# CPU_power.net
KiCad netlist of a schematic drawn in Altium Designer
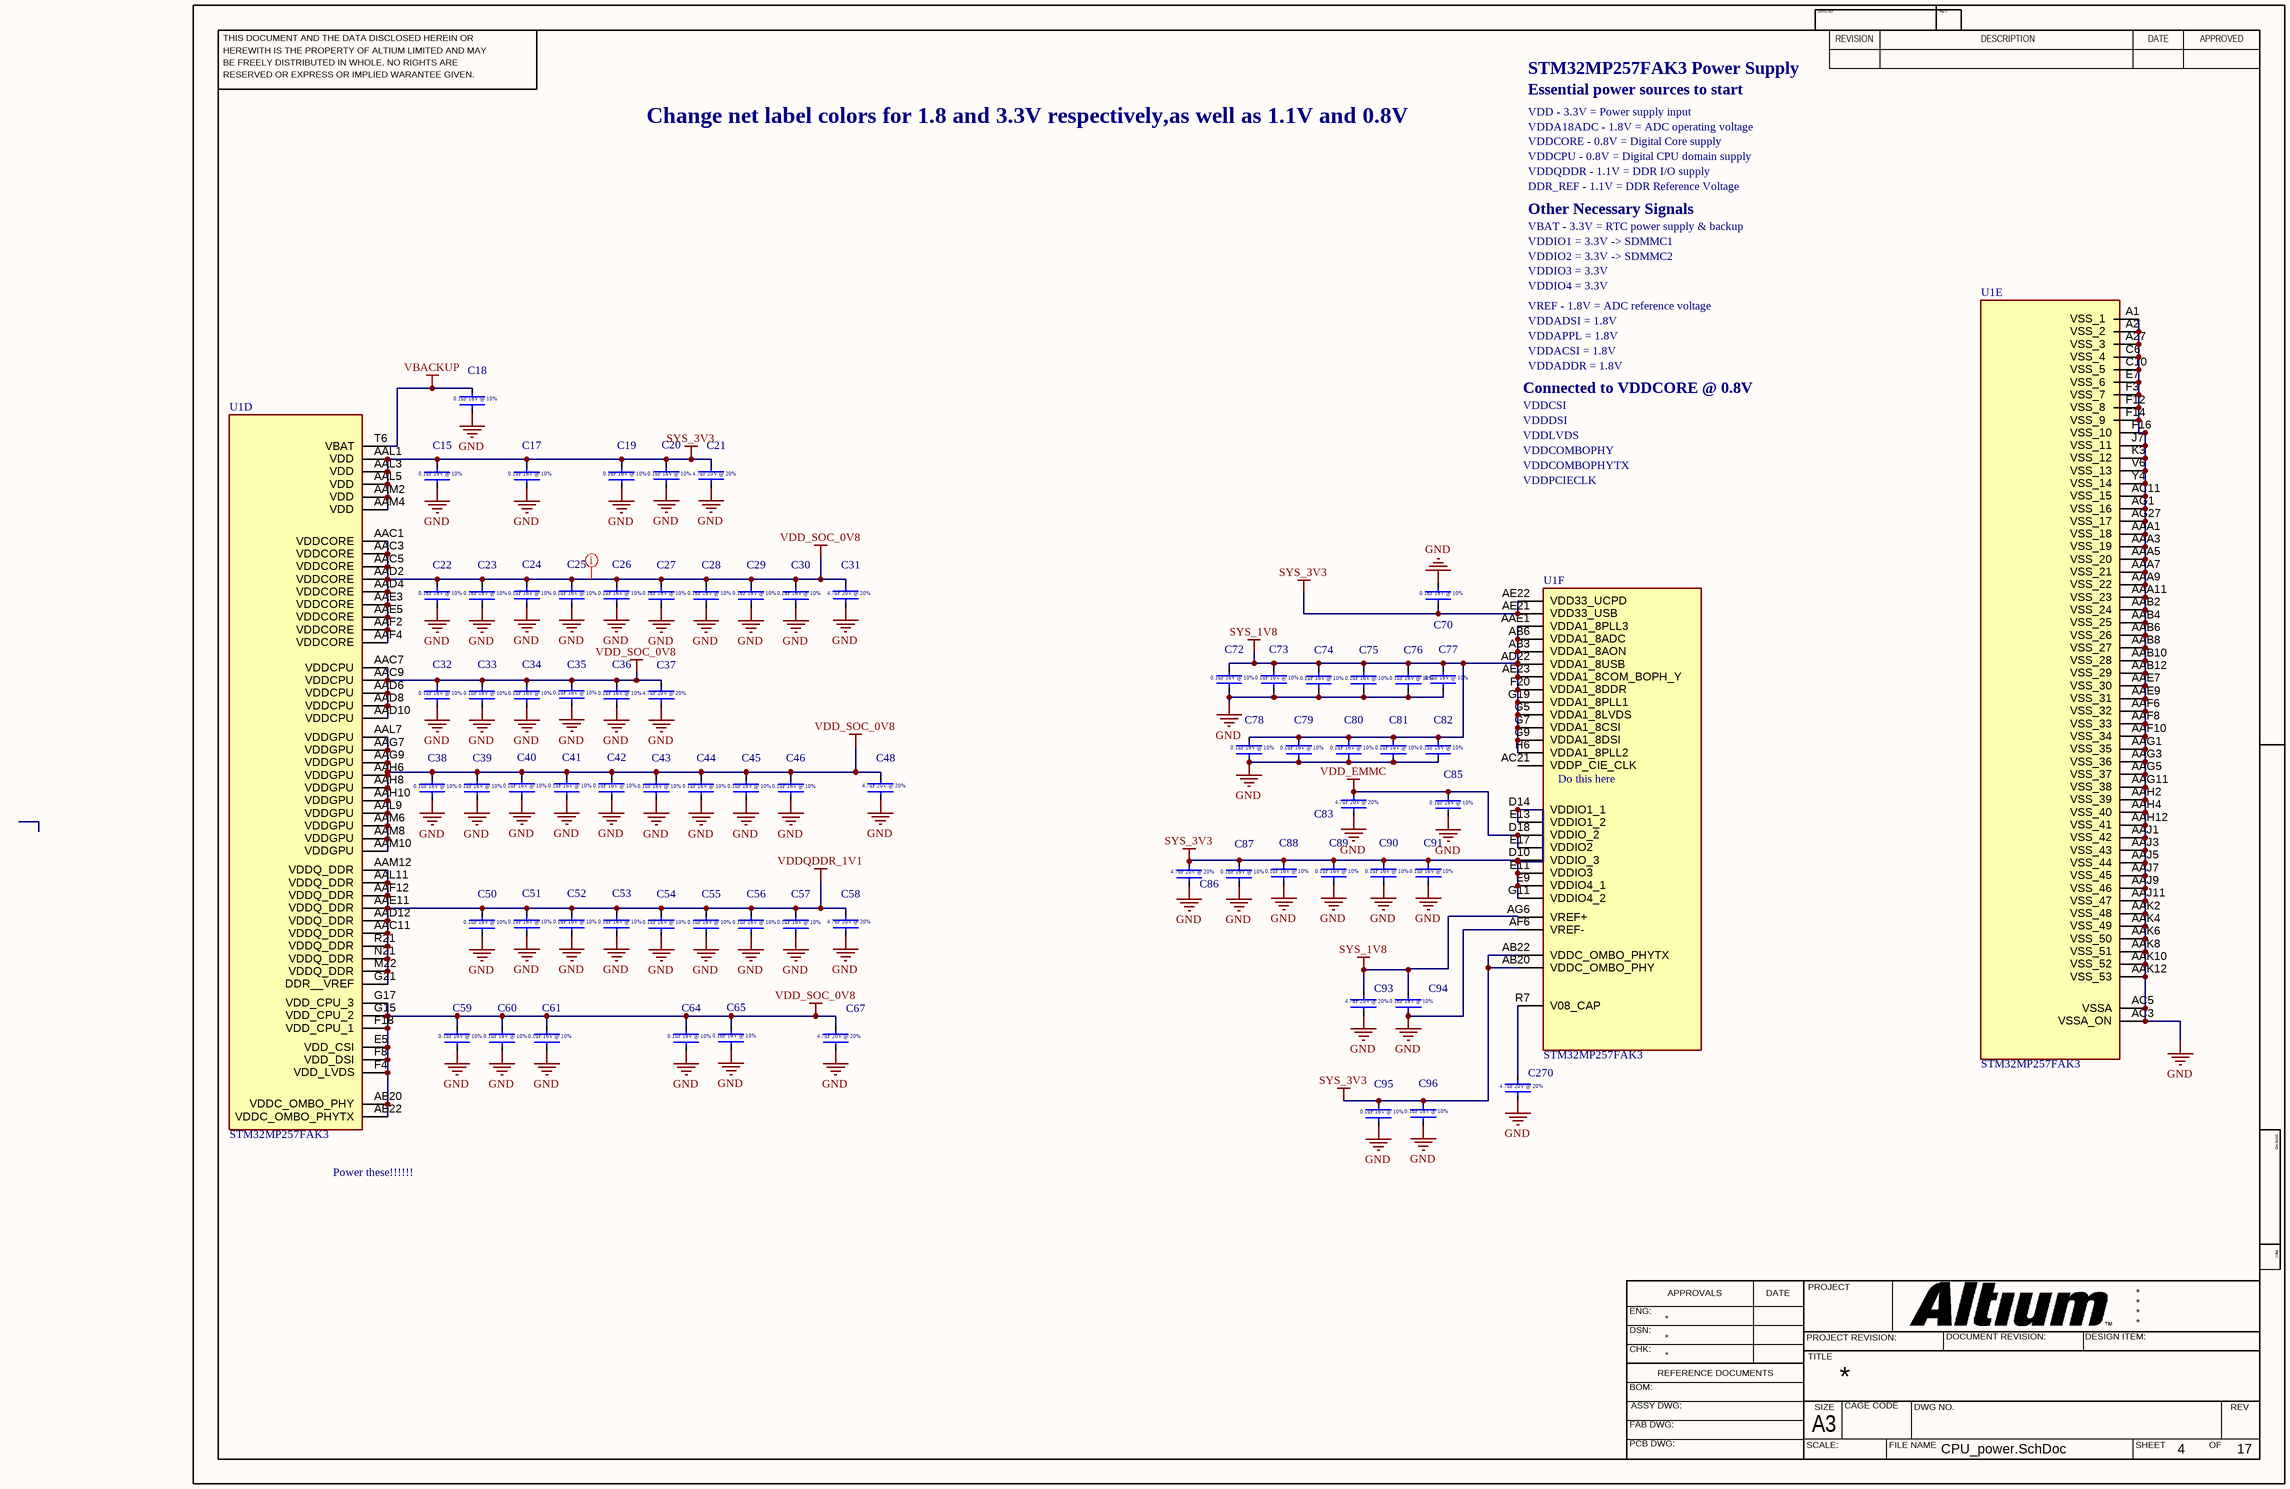
[diagram p0: CPU_power.SchDoc]

(export (version "E")
  (design (tool "Eeschema 10.0.6"))
  (components
    (comp (ref "C15")
      (value "0.1uF")
      (footprint "CAPC0603X03L")
      (libsource (lib "Gesturelink Schematic Library") (part "GRM033R61E104KE14J"))
    )
    (comp (ref "C17")
      (value "0.1uF")
      (footprint "CAPC0603X03L")
      (libsource (lib "Gesturelink Schematic Library") (part "GRM033R61E104KE14J"))
    )
    (comp (ref "C18")
      (value "0.1uF")
      (footprint "CAPC0603X03L")
      (libsource (lib "Gesturelink Schematic Library") (part "GRM033R61E104KE14J"))
    )
    (comp (ref "C19")
      (value "0.1uF")
      (footprint "CAPC0603X03L")
      (libsource (lib "Gesturelink Schematic Library") (part "GRM033R61E104KE14J"))
    )
    (comp (ref "C20")
      (value "0.1uF")
      (footprint "CAPC0603X03L")
      (libsource (lib "Gesturelink Schematic Library") (part "GRM033R61E104KE14J"))
    )
    (comp (ref "C21")
      (value "4.7uF")
      (footprint "CAPC1005X06L")
      (description "4.7 µF ±20% 16V Ceramic Capacitor X5R 0402 (1005 Metric)")
      (libsource (lib "Gesturelink Schematic Library") (part "CL05A475MO5NUNC"))
    )
    (comp (ref "C22")
      (value "0.1uF")
      (footprint "CAPC0603X03L")
      (libsource (lib "Gesturelink Schematic Library") (part "GRM033R61E104KE14J"))
    )
    (comp (ref "C23")
      (value "0.1uF")
      (footprint "CAPC0603X03L")
      (libsource (lib "Gesturelink Schematic Library") (part "GRM033R61E104KE14J"))
    )
    (comp (ref "C24")
      (value "0.1uF")
      (footprint "CAPC0603X03L")
      (libsource (lib "Gesturelink Schematic Library") (part "GRM033R61E104KE14J"))
    )
    (comp (ref "C25")
      (value "0.1uF")
      (footprint "CAPC0603X03L")
      (libsource (lib "Gesturelink Schematic Library") (part "GRM033R61E104KE14J"))
    )
    (comp (ref "C26")
      (value "0.1uF")
      (footprint "CAPC0603X03L")
      (libsource (lib "Gesturelink Schematic Library") (part "GRM033R61E104KE14J"))
    )
    (comp (ref "C27")
      (value "0.1uF")
      (footprint "CAPC0603X03L")
      (libsource (lib "Gesturelink Schematic Library") (part "GRM033R61E104KE14J"))
    )
    (comp (ref "C28")
      (value "0.1uF")
      (footprint "CAPC0603X03L")
      (libsource (lib "Gesturelink Schematic Library") (part "GRM033R61E104KE14J"))
    )
    (comp (ref "C29")
      (value "0.1uF")
      (footprint "CAPC0603X03L")
      (libsource (lib "Gesturelink Schematic Library") (part "GRM033R61E104KE14J"))
    )
    (comp (ref "C30")
      (value "0.1uF")
      (footprint "CAPC0603X03L")
      (libsource (lib "Gesturelink Schematic Library") (part "GRM033R61E104KE14J"))
    )
    (comp (ref "C31")
      (value "4.7uF")
      (footprint "CAPC1005X06L")
      (description "4.7 µF ±20% 16V Ceramic Capacitor X5R 0402 (1005 Metric)")
      (libsource (lib "Gesturelink Schematic Library") (part "CL05A475MO5NUNC"))
    )
    (comp (ref "C32")
      (value "0.1uF")
      (footprint "CAPC0603X03L")
      (libsource (lib "Gesturelink Schematic Library") (part "GRM033R61E104KE14J"))
    )
    (comp (ref "C33")
      (value "0.1uF")
      (footprint "CAPC0603X03L")
      (libsource (lib "Gesturelink Schematic Library") (part "GRM033R61E104KE14J"))
    )
    (comp (ref "C34")
      (value "0.1uF")
      (footprint "CAPC0603X03L")
      (libsource (lib "Gesturelink Schematic Library") (part "GRM033R61E104KE14J"))
    )
    (comp (ref "C35")
      (value "0.1uF")
      (footprint "CAPC0603X03L")
      (libsource (lib "Gesturelink Schematic Library") (part "GRM033R61E104KE14J"))
    )
    (comp (ref "C36")
      (value "0.1uF")
      (footprint "CAPC0603X03L")
      (libsource (lib "Gesturelink Schematic Library") (part "GRM033R61E104KE14J"))
    )
    (comp (ref "C37")
      (value "4.7uF")
      (footprint "CAPC1005X06L")
      (description "4.7 µF ±20% 16V Ceramic Capacitor X5R 0402 (1005 Metric)")
      (libsource (lib "Gesturelink Schematic Library") (part "CL05A475MO5NUNC"))
    )
    (comp (ref "C38")
      (value "0.1uF")
      (footprint "CAPC0603X03L")
      (libsource (lib "Gesturelink Schematic Library") (part "GRM033R61E104KE14J"))
    )
    (comp (ref "C39")
      (value "0.1uF")
      (footprint "CAPC0603X03L")
      (libsource (lib "Gesturelink Schematic Library") (part "GRM033R61E104KE14J"))
    )
    (comp (ref "C40")
      (value "0.1uF")
      (footprint "CAPC0603X03L")
      (libsource (lib "Gesturelink Schematic Library") (part "GRM033R61E104KE14J"))
    )
    (comp (ref "C41")
      (value "0.1uF")
      (footprint "CAPC0603X03L")
      (libsource (lib "Gesturelink Schematic Library") (part "GRM033R61E104KE14J"))
    )
    (comp (ref "C42")
      (value "0.1uF")
      (footprint "CAPC0603X03L")
      (libsource (lib "Gesturelink Schematic Library") (part "GRM033R61E104KE14J"))
    )
    (comp (ref "C43")
      (value "0.1uF")
      (footprint "CAPC0603X03L")
      (libsource (lib "Gesturelink Schematic Library") (part "GRM033R61E104KE14J"))
    )
    (comp (ref "C44")
      (value "0.1uF")
      (footprint "CAPC0603X03L")
      (libsource (lib "Gesturelink Schematic Library") (part "GRM033R61E104KE14J"))
    )
    (comp (ref "C45")
      (value "0.1uF")
      (footprint "CAPC0603X03L")
      (libsource (lib "Gesturelink Schematic Library") (part "GRM033R61E104KE14J"))
    )
    (comp (ref "C46")
      (value "0.1uF")
      (footprint "CAPC0603X03L")
      (libsource (lib "Gesturelink Schematic Library") (part "GRM033R61E104KE14J"))
    )
    (comp (ref "C48")
      (value "4.7uF")
      (footprint "CAPC1005X06L")
      (description "4.7 µF ±20% 16V Ceramic Capacitor X5R 0402 (1005 Metric)")
      (libsource (lib "Gesturelink Schematic Library") (part "CL05A475MO5NUNC"))
    )
    (comp (ref "C50")
      (value "0.1uF")
      (footprint "CAPC0603X03L")
      (libsource (lib "Gesturelink Schematic Library") (part "GRM033R61E104KE14J"))
    )
    (comp (ref "C51")
      (value "0.1uF")
      (footprint "CAPC0603X03L")
      (libsource (lib "Gesturelink Schematic Library") (part "GRM033R61E104KE14J"))
    )
    (comp (ref "C52")
      (value "0.1uF")
      (footprint "CAPC0603X03L")
      (libsource (lib "Gesturelink Schematic Library") (part "GRM033R61E104KE14J"))
    )
    (comp (ref "C53")
      (value "0.1uF")
      (footprint "CAPC0603X03L")
      (libsource (lib "Gesturelink Schematic Library") (part "GRM033R61E104KE14J"))
    )
    (comp (ref "C54")
      (value "0.1uF")
      (footprint "CAPC0603X03L")
      (libsource (lib "Gesturelink Schematic Library") (part "GRM033R61E104KE14J"))
    )
    (comp (ref "C55")
      (value "0.1uF")
      (footprint "CAPC0603X03L")
      (libsource (lib "Gesturelink Schematic Library") (part "GRM033R61E104KE14J"))
    )
    (comp (ref "C56")
      (value "0.1uF")
      (footprint "CAPC0603X03L")
      (libsource (lib "Gesturelink Schematic Library") (part "GRM033R61E104KE14J"))
    )
    (comp (ref "C57")
      (value "0.1uF")
      (footprint "CAPC0603X03L")
      (libsource (lib "Gesturelink Schematic Library") (part "GRM033R61E104KE14J"))
    )
    (comp (ref "C58")
      (value "4.7uF")
      (footprint "CAPC1005X06L")
      (description "4.7 µF ±20% 16V Ceramic Capacitor X5R 0402 (1005 Metric)")
      (libsource (lib "Gesturelink Schematic Library") (part "CL05A475MO5NUNC"))
    )
    (comp (ref "C59")
      (value "0.1uF")
      (footprint "CAPC0603X03L")
      (libsource (lib "Gesturelink Schematic Library") (part "GRM033R61E104KE14J"))
    )
    (comp (ref "C60")
      (value "0.1uF")
      (footprint "CAPC0603X03L")
      (libsource (lib "Gesturelink Schematic Library") (part "GRM033R61E104KE14J"))
    )
    (comp (ref "C61")
      (value "0.1uF")
      (footprint "CAPC0603X03L")
      (libsource (lib "Gesturelink Schematic Library") (part "GRM033R61E104KE14J"))
    )
    (comp (ref "C64")
      (value "0.1uF")
      (footprint "CAPC0603X03L")
      (libsource (lib "Gesturelink Schematic Library") (part "GRM033R61E104KE14J"))
    )
    (comp (ref "C65")
      (value "0.1uF")
      (footprint "CAPC0603X03L")
      (libsource (lib "Gesturelink Schematic Library") (part "GRM033R61E104KE14J"))
    )
    (comp (ref "C67")
      (value "4.7uF")
      (footprint "CAPC1005X06L")
      (description "4.7 µF ±20% 16V Ceramic Capacitor X5R 0402 (1005 Metric)")
      (libsource (lib "Gesturelink Schematic Library") (part "CL05A475MO5NUNC"))
    )
    (comp (ref "C70")
      (value "0.1uF")
      (footprint "CAPC0603X03L")
      (libsource (lib "Gesturelink Schematic Library") (part "GRM033R61E104KE14J"))
    )
    (comp (ref "C72")
      (value "0.1uF")
      (footprint "CAPC0603X03L")
      (libsource (lib "Gesturelink Schematic Library") (part "GRM033R61E104KE14J"))
    )
    (comp (ref "C73")
      (value "0.1uF")
      (footprint "CAPC0603X03L")
      (libsource (lib "Gesturelink Schematic Library") (part "GRM033R61E104KE14J"))
    )
    (comp (ref "C74")
      (value "0.1uF")
      (footprint "CAPC0603X03L")
      (libsource (lib "Gesturelink Schematic Library") (part "GRM033R61E104KE14J"))
    )
    (comp (ref "C75")
      (value "0.1uF")
      (footprint "CAPC0603X03L")
      (libsource (lib "Gesturelink Schematic Library") (part "GRM033R61E104KE14J"))
    )
    (comp (ref "C76")
      (value "0.1uF")
      (footprint "CAPC0603X03L")
      (libsource (lib "Gesturelink Schematic Library") (part "GRM033R61E104KE14J"))
    )
    (comp (ref "C77")
      (value "0.1uF")
      (footprint "CAPC0603X03L")
      (libsource (lib "Gesturelink Schematic Library") (part "GRM033R61E104KE14J"))
    )
    (comp (ref "C78")
      (value "0.1uF")
      (footprint "CAPC0603X03L")
      (libsource (lib "Gesturelink Schematic Library") (part "GRM033R61E104KE14J"))
    )
    (comp (ref "C79")
      (value "0.1uF")
      (footprint "CAPC0603X03L")
      (libsource (lib "Gesturelink Schematic Library") (part "GRM033R61E104KE14J"))
    )
    (comp (ref "C80")
      (value "0.1uF")
      (footprint "CAPC0603X03L")
      (libsource (lib "Gesturelink Schematic Library") (part "GRM033R61E104KE14J"))
    )
    (comp (ref "C81")
      (value "0.1uF")
      (footprint "CAPC0603X03L")
      (libsource (lib "Gesturelink Schematic Library") (part "GRM033R61E104KE14J"))
    )
    (comp (ref "C82")
      (value "0.1uF")
      (footprint "CAPC0603X03L")
      (libsource (lib "Gesturelink Schematic Library") (part "GRM033R61E104KE14J"))
    )
    (comp (ref "C83")
      (value "4.7uF")
      (footprint "CAPC1005X06L")
      (description "4.7 µF ±20% 16V Ceramic Capacitor X5R 0402 (1005 Metric)")
      (libsource (lib "Gesturelink Schematic Library") (part "CL05A475MO5NUNC"))
    )
    (comp (ref "C85")
      (value "0.1uF")
      (footprint "CAPC0603X03L")
      (libsource (lib "Gesturelink Schematic Library") (part "GRM033R61E104KE14J"))
    )
    (comp (ref "C86")
      (value "4.7uF")
      (footprint "CAPC1005X06L")
      (description "4.7 µF ±20% 16V Ceramic Capacitor X5R 0402 (1005 Metric)")
      (libsource (lib "Gesturelink Schematic Library") (part "CL05A475MO5NUNC"))
    )
    (comp (ref "C87")
      (value "0.1uF")
      (footprint "CAPC0603X03L")
      (libsource (lib "Gesturelink Schematic Library") (part "GRM033R61E104KE14J"))
    )
    (comp (ref "C88")
      (value "0.1uF")
      (footprint "CAPC0603X03L")
      (libsource (lib "Gesturelink Schematic Library") (part "GRM033R61E104KE14J"))
    )
    (comp (ref "C89")
      (value "0.1uF")
      (footprint "CAPC0603X03L")
      (libsource (lib "Gesturelink Schematic Library") (part "GRM033R61E104KE14J"))
    )
    (comp (ref "C90")
      (value "0.1uF")
      (footprint "CAPC0603X03L")
      (libsource (lib "Gesturelink Schematic Library") (part "GRM033R61E104KE14J"))
    )
    (comp (ref "C91")
      (value "0.1uF")
      (footprint "CAPC0603X03L")
      (libsource (lib "Gesturelink Schematic Library") (part "GRM033R61E104KE14J"))
    )
    (comp (ref "C93")
      (value "4.7uF")
      (footprint "CAPC1005X06L")
      (description "4.7 µF ±20% 16V Ceramic Capacitor X5R 0402 (1005 Metric)")
      (libsource (lib "Gesturelink Schematic Library") (part "CL05A475MO5NUNC"))
    )
    (comp (ref "C94")
      (value "0.1uF")
      (footprint "CAPC0603X03L")
      (libsource (lib "Gesturelink Schematic Library") (part "GRM033R61E104KE14J"))
    )
    (comp (ref "C95")
      (value "0.1uF")
      (footprint "CAPC0603X03L")
      (libsource (lib "Gesturelink Schematic Library") (part "GRM033R61E104KE14J"))
    )
    (comp (ref "C96")
      (value "0.1uF")
      (footprint "CAPC0603X03L")
      (libsource (lib "Gesturelink Schematic Library") (part "GRM033R61E104KE14J"))
    )
    (comp (ref "C270")
      (value "4.7uF")
      (footprint "CAPC1005X06L")
      (description "4.7 µF ±20% 16V Ceramic Capacitor X5R 0402 (1005 Metric)")
      (libsource (lib "Gesturelink Schematic Library") (part "CL05A475MO5NUNC"))
    )
    (comp (ref "U1")
      (value "STM32MP257FAK3")
      (footprint "SamacSys:STM32MP257FAK3")
      (description "Integrated Circuit")
      (fields (field (name "MOUSER PART NUMBER") "511-STM32MP257FAK3"))
      (libsource (lib "Gesturelink Schematic Library") (part "STM32MP257FAK3"))
    )
  )
  (nets
    (net (code "1") (name "GND") (class "Default")
      (node (ref "C15") (pin "1") (pinfunction "1_1") (pintype "passive"))
      (node (ref "C17") (pin "1") (pinfunction "1_1") (pintype "passive"))
      (node (ref "C18") (pin "1") (pinfunction "1_1") (pintype "passive"))
      (node (ref "C19") (pin "1") (pinfunction "1_1") (pintype "passive"))
      (node (ref "C20") (pin "1") (pinfunction "1_1") (pintype "passive"))
      (node (ref "C21") (pin "1") (pinfunction "1_1") (pintype "passive"))
      (node (ref "C22") (pin "1") (pinfunction "1_1") (pintype "passive"))
      (node (ref "C23") (pin "1") (pinfunction "1_1") (pintype "passive"))
      (node (ref "C24") (pin "1") (pinfunction "1_1") (pintype "passive"))
      (node (ref "C25") (pin "1") (pinfunction "1_1") (pintype "passive"))
      (node (ref "C26") (pin "1") (pinfunction "1_1") (pintype "passive"))
      (node (ref "C27") (pin "1") (pinfunction "1_1") (pintype "passive"))
      (node (ref "C270") (pin "1") (pinfunction "1_1") (pintype "passive"))
      (node (ref "C28") (pin "1") (pinfunction "1_1") (pintype "passive"))
      (node (ref "C29") (pin "1") (pinfunction "1_1") (pintype "passive"))
      (node (ref "C30") (pin "1") (pinfunction "1_1") (pintype "passive"))
      (node (ref "C31") (pin "1") (pinfunction "1_1") (pintype "passive"))
      (node (ref "C32") (pin "1") (pinfunction "1_1") (pintype "passive"))
      (node (ref "C33") (pin "1") (pinfunction "1_1") (pintype "passive"))
      (node (ref "C34") (pin "1") (pinfunction "1_1") (pintype "passive"))
      (node (ref "C35") (pin "1") (pinfunction "1_1") (pintype "passive"))
      (node (ref "C36") (pin "1") (pinfunction "1_1") (pintype "passive"))
      (node (ref "C37") (pin "1") (pinfunction "1_1") (pintype "passive"))
      (node (ref "C38") (pin "1") (pinfunction "1_1") (pintype "passive"))
      (node (ref "C39") (pin "1") (pinfunction "1_1") (pintype "passive"))
      (node (ref "C40") (pin "1") (pinfunction "1_1") (pintype "passive"))
      (node (ref "C41") (pin "1") (pinfunction "1_1") (pintype "passive"))
      (node (ref "C42") (pin "1") (pinfunction "1_1") (pintype "passive"))
      (node (ref "C43") (pin "1") (pinfunction "1_1") (pintype "passive"))
      (node (ref "C44") (pin "1") (pinfunction "1_1") (pintype "passive"))
      (node (ref "C45") (pin "1") (pinfunction "1_1") (pintype "passive"))
      (node (ref "C46") (pin "1") (pinfunction "1_1") (pintype "passive"))
      (node (ref "C48") (pin "1") (pinfunction "1_1") (pintype "passive"))
      (node (ref "C50") (pin "1") (pinfunction "1_1") (pintype "passive"))
      (node (ref "C51") (pin "1") (pinfunction "1_1") (pintype "passive"))
      (node (ref "C52") (pin "1") (pinfunction "1_1") (pintype "passive"))
      (node (ref "C53") (pin "1") (pinfunction "1_1") (pintype "passive"))
      (node (ref "C54") (pin "1") (pinfunction "1_1") (pintype "passive"))
      (node (ref "C55") (pin "1") (pinfunction "1_1") (pintype "passive"))
      (node (ref "C56") (pin "1") (pinfunction "1_1") (pintype "passive"))
      (node (ref "C57") (pin "1") (pinfunction "1_1") (pintype "passive"))
      (node (ref "C58") (pin "1") (pinfunction "1_1") (pintype "passive"))
      (node (ref "C59") (pin "1") (pinfunction "1_1") (pintype "passive"))
      (node (ref "C60") (pin "1") (pinfunction "1_1") (pintype "passive"))
      (node (ref "C61") (pin "1") (pinfunction "1_1") (pintype "passive"))
      (node (ref "C64") (pin "1") (pinfunction "1_1") (pintype "passive"))
      (node (ref "C65") (pin "1") (pinfunction "1_1") (pintype "passive"))
      (node (ref "C67") (pin "1") (pinfunction "1_1") (pintype "passive"))
      (node (ref "C70") (pin "2") (pinfunction "2_2") (pintype "passive"))
      (node (ref "C72") (pin "1") (pinfunction "1_1") (pintype "passive"))
      (node (ref "C73") (pin "1") (pinfunction "1_1") (pintype "passive"))
      (node (ref "C74") (pin "1") (pinfunction "1_1") (pintype "passive"))
      (node (ref "C75") (pin "1") (pinfunction "1_1") (pintype "passive"))
      (node (ref "C76") (pin "1") (pinfunction "1_1") (pintype "passive"))
      (node (ref "C77") (pin "1") (pinfunction "1_1") (pintype "passive"))
      (node (ref "C78") (pin "1") (pinfunction "1_1") (pintype "passive"))
      (node (ref "C79") (pin "1") (pinfunction "1_1") (pintype "passive"))
      (node (ref "C80") (pin "1") (pinfunction "1_1") (pintype "passive"))
      (node (ref "C81") (pin "1") (pinfunction "1_1") (pintype "passive"))
      (node (ref "C82") (pin "1") (pinfunction "1_1") (pintype "passive"))
      (node (ref "C83") (pin "1") (pinfunction "1_1") (pintype "passive"))
      (node (ref "C85") (pin "1") (pinfunction "1_1") (pintype "passive"))
      (node (ref "C86") (pin "1") (pinfunction "1_1") (pintype "passive"))
      (node (ref "C87") (pin "1") (pinfunction "1_1") (pintype "passive"))
      (node (ref "C88") (pin "1") (pinfunction "1_1") (pintype "passive"))
      (node (ref "C89") (pin "1") (pinfunction "1_1") (pintype "passive"))
      (node (ref "C90") (pin "1") (pinfunction "1_1") (pintype "passive"))
      (node (ref "C91") (pin "1") (pinfunction "1_1") (pintype "passive"))
      (node (ref "C93") (pin "1") (pinfunction "1_1") (pintype "passive"))
      (node (ref "C94") (pin "1") (pinfunction "1_1") (pintype "passive"))
      (node (ref "C95") (pin "1") (pinfunction "1_1") (pintype "passive"))
      (node (ref "C96") (pin "1") (pinfunction "1_1") (pintype "passive"))
      (node (ref "U1") (pin "A1") (pinfunction "VSS_1_A1") (pintype "passive"))
      (node (ref "U1") (pin "A2") (pinfunction "VSS_2_A2") (pintype "passive"))
      (node (ref "U1") (pin "A27") (pinfunction "VSS_3_A27") (pintype "passive"))
      (node (ref "U1") (pin "AAA1") (pinfunction "VSS_18_AAA1") (pintype "passive"))
      (node (ref "U1") (pin "AAA11") (pinfunction "VSS_23_AAA11") (pintype "passive"))
      (node (ref "U1") (pin "AAA3") (pinfunction "VSS_19_AAA3") (pintype "passive"))
      (node (ref "U1") (pin "AAA5") (pinfunction "VSS_20_AAA5") (pintype "passive"))
      (node (ref "U1") (pin "AAA7") (pinfunction "VSS_21_AAA7") (pintype "passive"))
      (node (ref "U1") (pin "AAA9") (pinfunction "VSS_22_AAA9") (pintype "passive"))
      (node (ref "U1") (pin "AAB10") (pinfunction "VSS_28_AAB10") (pintype "passive"))
      (node (ref "U1") (pin "AAB12") (pinfunction "VSS_29_AAB12") (pintype "passive"))
      (node (ref "U1") (pin "AAB2") (pinfunction "VSS_24_AAB2") (pintype "passive"))
      (node (ref "U1") (pin "AAB4") (pinfunction "VSS_25_AAB4") (pintype "passive"))
      (node (ref "U1") (pin "AAB6") (pinfunction "VSS_26_AAB6") (pintype "passive"))
      (node (ref "U1") (pin "AAB8") (pinfunction "VSS_27_AAB8") (pintype "passive"))
      (node (ref "U1") (pin "AAE7") (pinfunction "VSS_30_AAE7") (pintype "passive"))
      (node (ref "U1") (pin "AAE9") (pinfunction "VSS_31_AAE9") (pintype "passive"))
      (node (ref "U1") (pin "AAF10") (pinfunction "VSS_34_AAF10") (pintype "passive"))
      (node (ref "U1") (pin "AAF6") (pinfunction "VSS_32_AAF6") (pintype "passive"))
      (node (ref "U1") (pin "AAF8") (pinfunction "VSS_33_AAF8") (pintype "passive"))
      (node (ref "U1") (pin "AAG1") (pinfunction "VSS_35_AAG1") (pintype "passive"))
      (node (ref "U1") (pin "AAG11") (pinfunction "VSS_38_AAG11") (pintype "passive"))
      (node (ref "U1") (pin "AAG3") (pinfunction "VSS_36_AAG3") (pintype "passive"))
      (node (ref "U1") (pin "AAG5") (pinfunction "VSS_37_AAG5") (pintype "passive"))
      (node (ref "U1") (pin "AAH12") (pinfunction "VSS_41_AAH12") (pintype "passive"))
      (node (ref "U1") (pin "AAH2") (pinfunction "VSS_39_AAH2") (pintype "passive"))
      (node (ref "U1") (pin "AAH4") (pinfunction "VSS_40_AAH4") (pintype "passive"))
      (node (ref "U1") (pin "AAJ1") (pinfunction "VSS_42_AAJ1") (pintype "passive"))
      (node (ref "U1") (pin "AAJ11") (pinfunction "VSS_47_AAJ11") (pintype "passive"))
      (node (ref "U1") (pin "AAJ3") (pinfunction "VSS_43_AAJ3") (pintype "passive"))
      (node (ref "U1") (pin "AAJ5") (pinfunction "VSS_44_AAJ5") (pintype "passive"))
      (node (ref "U1") (pin "AAJ7") (pinfunction "VSS_45_AAJ7") (pintype "passive"))
      (node (ref "U1") (pin "AAJ9") (pinfunction "VSS_46_AAJ9") (pintype "passive"))
      (node (ref "U1") (pin "AAK10") (pinfunction "VSS_52_AAK10") (pintype "passive"))
      (node (ref "U1") (pin "AAK12") (pinfunction "VSS_53_AAK12") (pintype "passive"))
      (node (ref "U1") (pin "AAK2") (pinfunction "VSS_48_AAK2") (pintype "passive"))
      (node (ref "U1") (pin "AAK4") (pinfunction "VSS_49_AAK4") (pintype "passive"))
      (node (ref "U1") (pin "AAK6") (pinfunction "VSS_50_AAK6") (pintype "passive"))
      (node (ref "U1") (pin "AAK8") (pinfunction "VSS_51_AAK8") (pintype "passive"))
      (node (ref "U1") (pin "AC11") (pinfunction "VSS_15_AC11") (pintype "passive"))
      (node (ref "U1") (pin "AC3") (pinfunction "VSSA_ON_AC3") (pintype "passive"))
      (node (ref "U1") (pin "AC5") (pinfunction "VSSA_AC5") (pintype "passive"))
      (node (ref "U1") (pin "AF6") (pinfunction "VREF-_AF6") (pintype "passive"))
      (node (ref "U1") (pin "AG1") (pinfunction "VSS_16_AG1") (pintype "passive"))
      (node (ref "U1") (pin "AG27") (pinfunction "VSS_17_AG27") (pintype "passive"))
      (node (ref "U1") (pin "C10") (pinfunction "VSS_5_C10") (pintype "passive"))
      (node (ref "U1") (pin "C6") (pinfunction "VSS_4_C6") (pintype "passive"))
      (node (ref "U1") (pin "E7") (pinfunction "VSS_6_E7") (pintype "passive"))
      (node (ref "U1") (pin "F12") (pinfunction "VSS_8_F12") (pintype "passive"))
      (node (ref "U1") (pin "F14") (pinfunction "VSS_9_F14") (pintype "passive"))
      (node (ref "U1") (pin "F16") (pinfunction "VSS_10_F16") (pintype "passive"))
      (node (ref "U1") (pin "F3") (pinfunction "VSS_7_F3") (pintype "passive"))
      (node (ref "U1") (pin "J7") (pinfunction "VSS_11_J7") (pintype "passive"))
      (node (ref "U1") (pin "K3") (pinfunction "VSS_12_K3") (pintype "passive"))
      (node (ref "U1") (pin "V6") (pinfunction "VSS_13_V6") (pintype "passive"))
      (node (ref "U1") (pin "Y4") (pinfunction "VSS_14_Y4") (pintype "passive"))
    )
    (net (code "2") (name "Net-(U1F-V08_CAP)") (class "Default")
      (node (ref "C270") (pin "2") (pinfunction "2_2") (pintype "passive"))
      (node (ref "U1") (pin "R7") (pinfunction "V08_CAP_R7") (pintype "passive"))
    )
    (net (code "3") (name "SYS_1V8") (class "Default")
      (node (ref "C72") (pin "2") (pinfunction "2_2") (pintype "passive"))
      (node (ref "C73") (pin "2") (pinfunction "2_2") (pintype "passive"))
      (node (ref "C74") (pin "2") (pinfunction "2_2") (pintype "passive"))
      (node (ref "C75") (pin "2") (pinfunction "2_2") (pintype "passive"))
      (node (ref "C76") (pin "2") (pinfunction "2_2") (pintype "passive"))
      (node (ref "C77") (pin "2") (pinfunction "2_2") (pintype "passive"))
      (node (ref "C78") (pin "2") (pinfunction "2_2") (pintype "passive"))
      (node (ref "C79") (pin "2") (pinfunction "2_2") (pintype "passive"))
      (node (ref "C80") (pin "2") (pinfunction "2_2") (pintype "passive"))
      (node (ref "C81") (pin "2") (pinfunction "2_2") (pintype "passive"))
      (node (ref "C82") (pin "2") (pinfunction "2_2") (pintype "passive"))
      (node (ref "C93") (pin "2") (pinfunction "2_2") (pintype "passive"))
      (node (ref "C94") (pin "2") (pinfunction "2_2") (pintype "passive"))
      (node (ref "U1") (pin "AAE1") (pinfunction "VDDA1_8PLL3_AAE1") (pintype "passive"))
      (node (ref "U1") (pin "AB3") (pinfunction "VDDA1_8AON_AB3") (pintype "passive"))
      (node (ref "U1") (pin "AB6") (pinfunction "VDDA1_8ADC_AB6") (pintype "passive"))
      (node (ref "U1") (pin "AD22") (pinfunction "VDDA1_8USB_AD22") (pintype "passive"))
      (node (ref "U1") (pin "AE23") (pinfunction "VDDA1_8COM_BOPH_Y_AE23") (pintype "passive"))
      (node (ref "U1") (pin "AG6") (pinfunction "VREF+_AG6") (pintype "passive"))
      (node (ref "U1") (pin "F20") (pinfunction "VDDA1_8DDR_F20") (pintype "passive"))
      (node (ref "U1") (pin "G19") (pinfunction "VDDA1_8PLL1_G19") (pintype "passive"))
      (node (ref "U1") (pin "G5") (pinfunction "VDDA1_8LVDS_G5") (pintype "passive"))
      (node (ref "U1") (pin "G7") (pinfunction "VDDA1_8CSI_G7") (pintype "passive"))
      (node (ref "U1") (pin "G9") (pinfunction "VDDA1_8DSI_G9") (pintype "passive"))
      (node (ref "U1") (pin "H6") (pinfunction "VDDA1_8PLL2_H6") (pintype "passive"))
    )
    (net (code "4") (name "SYS_3V3") (class "Default")
      (node (ref "C15") (pin "2") (pinfunction "2_2") (pintype "passive"))
      (node (ref "C17") (pin "2") (pinfunction "2_2") (pintype "passive"))
      (node (ref "C19") (pin "2") (pinfunction "2_2") (pintype "passive"))
      (node (ref "C20") (pin "2") (pinfunction "2_2") (pintype "passive"))
      (node (ref "C21") (pin "2") (pinfunction "2_2") (pintype "passive"))
      (node (ref "C70") (pin "1") (pinfunction "1_1") (pintype "passive"))
      (node (ref "C86") (pin "2") (pinfunction "2_2") (pintype "passive"))
      (node (ref "C87") (pin "2") (pinfunction "2_2") (pintype "passive"))
      (node (ref "C88") (pin "2") (pinfunction "2_2") (pintype "passive"))
      (node (ref "C89") (pin "2") (pinfunction "2_2") (pintype "passive"))
      (node (ref "C90") (pin "2") (pinfunction "2_2") (pintype "passive"))
      (node (ref "C91") (pin "2") (pinfunction "2_2") (pintype "passive"))
      (node (ref "C95") (pin "2") (pinfunction "2_2") (pintype "passive"))
      (node (ref "C96") (pin "2") (pinfunction "2_2") (pintype "passive"))
      (node (ref "U1") (pin "AAL1") (pinfunction "VDD_AAL1") (pintype "passive"))
      (node (ref "U1") (pin "AAL3") (pinfunction "VDD_AAL3") (pintype "passive"))
      (node (ref "U1") (pin "AAL5") (pinfunction "VDD_AAL5") (pintype "passive"))
      (node (ref "U1") (pin "AAM2") (pinfunction "VDD_AAM2") (pintype "passive"))
      (node (ref "U1") (pin "AAM4") (pinfunction "VDD_AAM4") (pintype "passive"))
      (node (ref "U1") (pin "AB20") (pinfunction "VDDC_OMBO_PHY_AB20") (pintype "passive"))
      (node (ref "U1") (pin "AB22") (pinfunction "VDDC_OMBO_PHYTX_AB22") (pintype "passive"))
      (node (ref "U1") (pin "AE21") (pinfunction "VDD33_USB_AE21") (pintype "passive"))
      (node (ref "U1") (pin "AE22") (pinfunction "VDD33_UCPD_AE22") (pintype "passive"))
      (node (ref "U1") (pin "D10") (pinfunction "VDDIO_3_D10") (pintype "passive"))
      (node (ref "U1") (pin "D14") (pinfunction "VDDIO1_1_D14") (pintype "passive"))
      (node (ref "U1") (pin "E11") (pinfunction "VDDIO3_E11") (pintype "passive"))
      (node (ref "U1") (pin "E13") (pinfunction "VDDIO1_2_E13") (pintype "passive"))
      (node (ref "U1") (pin "E9") (pinfunction "VDDIO4_1_E9") (pintype "passive"))
      (node (ref "U1") (pin "G11") (pinfunction "VDDIO4_2_G11") (pintype "passive"))
    )
    (net (code "5") (name "VBACKUP") (class "Default")
      (node (ref "C18") (pin "2") (pinfunction "2_2") (pintype "passive"))
      (node (ref "U1") (pin "T6") (pinfunction "VBAT_T6") (pintype "passive"))
    )
    (net (code "6") (name "VDDQDDR_1V1") (class "Default")
      (node (ref "C50") (pin "2") (pinfunction "2_2") (pintype "passive"))
      (node (ref "C51") (pin "2") (pinfunction "2_2") (pintype "passive"))
      (node (ref "C52") (pin "2") (pinfunction "2_2") (pintype "passive"))
      (node (ref "C53") (pin "2") (pinfunction "2_2") (pintype "passive"))
      (node (ref "C54") (pin "2") (pinfunction "2_2") (pintype "passive"))
      (node (ref "C55") (pin "2") (pinfunction "2_2") (pintype "passive"))
      (node (ref "C56") (pin "2") (pinfunction "2_2") (pintype "passive"))
      (node (ref "C57") (pin "2") (pinfunction "2_2") (pintype "passive"))
      (node (ref "C58") (pin "2") (pinfunction "2_2") (pintype "passive"))
      (node (ref "U1") (pin "AAC11") (pinfunction "VDDQ_DDR_AAC11") (pintype "passive"))
      (node (ref "U1") (pin "AAD12") (pinfunction "VDDQ_DDR_AAD12") (pintype "passive"))
      (node (ref "U1") (pin "AAE11") (pinfunction "VDDQ_DDR_AAE11") (pintype "passive"))
      (node (ref "U1") (pin "AAF12") (pinfunction "VDDQ_DDR_AAF12") (pintype "passive"))
      (node (ref "U1") (pin "AAL11") (pinfunction "VDDQ_DDR_AAL11") (pintype "passive"))
      (node (ref "U1") (pin "AAM12") (pinfunction "VDDQ_DDR_AAM12") (pintype "passive"))
      (node (ref "U1") (pin "G21") (pinfunction "DDR__VREF_G21") (pintype "passive"))
      (node (ref "U1") (pin "M22") (pinfunction "VDDQ_DDR_M22") (pintype "passive"))
      (node (ref "U1") (pin "N21") (pinfunction "VDDQ_DDR_N21") (pintype "passive"))
      (node (ref "U1") (pin "R21") (pinfunction "VDDQ_DDR_R21") (pintype "passive"))
    )
    (net (code "7") (name "VDD_EMMC") (class "Default")
      (node (ref "C83") (pin "2") (pinfunction "2_2") (pintype "passive"))
      (node (ref "C85") (pin "2") (pinfunction "2_2") (pintype "passive"))
      (node (ref "U1") (pin "D18") (pinfunction "VDDIO_2_D18") (pintype "passive"))
      (node (ref "U1") (pin "E17") (pinfunction "VDDIO2_E17") (pintype "passive"))
    )
    (net (code "8") (name "VDD_SOC_0V8") (class "Default")
      (node (ref "C22") (pin "2") (pinfunction "2_2") (pintype "passive"))
      (node (ref "C23") (pin "2") (pinfunction "2_2") (pintype "passive"))
      (node (ref "C24") (pin "2") (pinfunction "2_2") (pintype "passive"))
      (node (ref "C25") (pin "2") (pinfunction "2_2") (pintype "passive"))
      (node (ref "C26") (pin "2") (pinfunction "2_2") (pintype "passive"))
      (node (ref "C27") (pin "2") (pinfunction "2_2") (pintype "passive"))
      (node (ref "C28") (pin "2") (pinfunction "2_2") (pintype "passive"))
      (node (ref "C29") (pin "2") (pinfunction "2_2") (pintype "passive"))
      (node (ref "C30") (pin "2") (pinfunction "2_2") (pintype "passive"))
      (node (ref "C31") (pin "2") (pinfunction "2_2") (pintype "passive"))
      (node (ref "C32") (pin "2") (pinfunction "2_2") (pintype "passive"))
      (node (ref "C33") (pin "2") (pinfunction "2_2") (pintype "passive"))
      (node (ref "C34") (pin "2") (pinfunction "2_2") (pintype "passive"))
      (node (ref "C35") (pin "2") (pinfunction "2_2") (pintype "passive"))
      (node (ref "C36") (pin "2") (pinfunction "2_2") (pintype "passive"))
      (node (ref "C37") (pin "2") (pinfunction "2_2") (pintype "passive"))
      (node (ref "C38") (pin "2") (pinfunction "2_2") (pintype "passive"))
      (node (ref "C39") (pin "2") (pinfunction "2_2") (pintype "passive"))
      (node (ref "C40") (pin "2") (pinfunction "2_2") (pintype "passive"))
      (node (ref "C41") (pin "2") (pinfunction "2_2") (pintype "passive"))
      (node (ref "C42") (pin "2") (pinfunction "2_2") (pintype "passive"))
      (node (ref "C43") (pin "2") (pinfunction "2_2") (pintype "passive"))
      (node (ref "C44") (pin "2") (pinfunction "2_2") (pintype "passive"))
      (node (ref "C45") (pin "2") (pinfunction "2_2") (pintype "passive"))
      (node (ref "C46") (pin "2") (pinfunction "2_2") (pintype "passive"))
      (node (ref "C48") (pin "2") (pinfunction "2_2") (pintype "passive"))
      (node (ref "C59") (pin "2") (pinfunction "2_2") (pintype "passive"))
      (node (ref "C60") (pin "2") (pinfunction "2_2") (pintype "passive"))
      (node (ref "C61") (pin "2") (pinfunction "2_2") (pintype "passive"))
      (node (ref "C64") (pin "2") (pinfunction "2_2") (pintype "passive"))
      (node (ref "C65") (pin "2") (pinfunction "2_2") (pintype "passive"))
      (node (ref "C67") (pin "2") (pinfunction "2_2") (pintype "passive"))
      (node (ref "U1") (pin "AAC1") (pinfunction "VDDCORE_AAC1") (pintype "passive"))
      (node (ref "U1") (pin "AAC3") (pinfunction "VDDCORE_AAC3") (pintype "passive"))
      (node (ref "U1") (pin "AAC5") (pinfunction "VDDCORE_AAC5") (pintype "passive"))
      (node (ref "U1") (pin "AAC7") (pinfunction "VDDCPU_AAC7") (pintype "passive"))
      (node (ref "U1") (pin "AAC9") (pinfunction "VDDCPU_AAC9") (pintype "passive"))
      (node (ref "U1") (pin "AAD10") (pinfunction "VDDCPU_AAD10") (pintype "passive"))
      (node (ref "U1") (pin "AAD2") (pinfunction "VDDCORE_AAD2") (pintype "passive"))
      (node (ref "U1") (pin "AAD4") (pinfunction "VDDCORE_AAD4") (pintype "passive"))
      (node (ref "U1") (pin "AAD6") (pinfunction "VDDCPU_AAD6") (pintype "passive"))
      (node (ref "U1") (pin "AAD8") (pinfunction "VDDCPU_AAD8") (pintype "passive"))
      (node (ref "U1") (pin "AAE3") (pinfunction "VDDCORE_AAE3") (pintype "passive"))
      (node (ref "U1") (pin "AAE5") (pinfunction "VDDCORE_AAE5") (pintype "passive"))
      (node (ref "U1") (pin "AAF2") (pinfunction "VDDCORE_AAF2") (pintype "passive"))
      (node (ref "U1") (pin "AAF4") (pinfunction "VDDCORE_AAF4") (pintype "passive"))
      (node (ref "U1") (pin "AAG7") (pinfunction "VDDGPU_AAG7") (pintype "passive"))
      (node (ref "U1") (pin "AAG9") (pinfunction "VDDGPU_AAG9") (pintype "passive"))
      (node (ref "U1") (pin "AAH10") (pinfunction "VDDGPU_AAH10") (pintype "passive"))
      (node (ref "U1") (pin "AAH6") (pinfunction "VDDGPU_AAH6") (pintype "passive"))
      (node (ref "U1") (pin "AAH8") (pinfunction "VDDGPU_AAH8") (pintype "passive"))
      (node (ref "U1") (pin "AAL7") (pinfunction "VDDGPU_AAL7") (pintype "passive"))
      (node (ref "U1") (pin "AAL9") (pinfunction "VDDGPU_AAL9") (pintype "passive"))
      (node (ref "U1") (pin "AAM10") (pinfunction "VDDGPU_AAM10") (pintype "passive"))
      (node (ref "U1") (pin "AAM6") (pinfunction "VDDGPU_AAM6") (pintype "passive"))
      (node (ref "U1") (pin "AAM8") (pinfunction "VDDGPU_AAM8") (pintype "passive"))
      (node (ref "U1") (pin "AB20") (pinfunction "VDDC_OMBO_PHY_AB20") (pintype "passive"))
      (node (ref "U1") (pin "AB22") (pinfunction "VDDC_OMBO_PHYTX_AB22") (pintype "passive"))
      (node (ref "U1") (pin "E5") (pinfunction "VDD_CSI_E5") (pintype "passive"))
      (node (ref "U1") (pin "F18") (pinfunction "VDD_CPU_1_F18") (pintype "passive"))
      (node (ref "U1") (pin "F4") (pinfunction "VDD_LVDS_F4") (pintype "passive"))
      (node (ref "U1") (pin "F8") (pinfunction "VDD_DSI_F8") (pintype "passive"))
      (node (ref "U1") (pin "G15") (pinfunction "VDD_CPU_2_G15") (pintype "passive"))
      (node (ref "U1") (pin "G17") (pinfunction "VDD_CPU_3_G17") (pintype "passive"))
    )
    (net (code "9") (name "unconnected-(U1F-VDDP_CIE_CLK-PadAC21)") (class "Default")
      (node (ref "U1") (pin "AC21") (pinfunction "VDDP_CIE_CLK_AC21") (pintype "passive"))
    )
  )
)
